# Flight_diagram.net
KiCad netlist of a schematic drawn in EAGLE
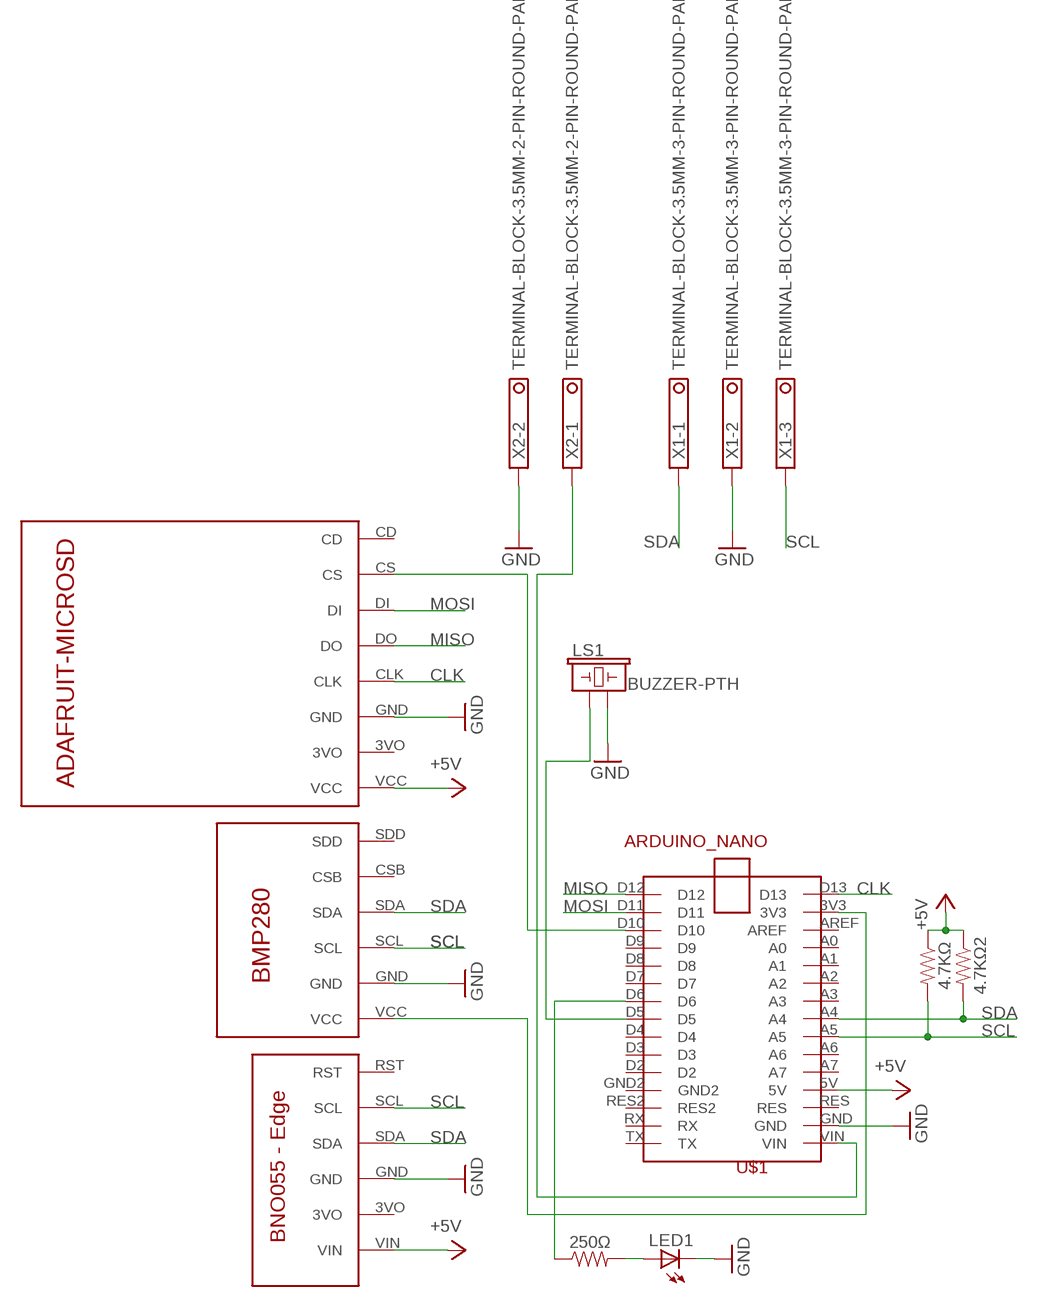
[diagram p0: schematic, sheet 1]

(export (version "E")
  (design (tool "Eeschema 10.0.6"))
  (components
    (comp (ref "4.7KΩ")
      (value "RESISTORAXIAL-0.3")
      (footprint "eagle-import:AXIAL-0.3")
      (libsource (lib "eagle-import") (part "RESISTORAXIAL-0.3"))
    )
    (comp (ref "4.7KΩ2")
      (value "RESISTORAXIAL-0.3")
      (footprint "eagle-import:AXIAL-0.3")
      (libsource (lib "eagle-import") (part "RESISTORAXIAL-0.3"))
    )
    (comp (ref "250Ω")
      (value "RESISTORAXIAL-0.3")
      (footprint "eagle-import:AXIAL-0.3")
      (libsource (lib "eagle-import") (part "RESISTORAXIAL-0.3"))
    )
    (comp (ref "LED1")
      (value "LED5MM")
      (footprint "eagle-import:LED5MM")
      (libsource (lib "eagle-import") (part "LED5MM"))
    )
    (comp (ref "LS1")
      (value "BUZZER-PTH")
      (footprint "eagle-import:BUZZER-12MM")
      (libsource (lib "eagle-import") (part "BUZZER-PTH"))
    )
    (comp (ref "U$1")
      (value "ARDUINO_NANO")
      (footprint "eagle-import:ARDUIN_NANO")
      (libsource (lib "eagle-import") (part "ARDUINO_NANO"))
    )
    (comp (ref "U$2")
      (value "BNO055")
      (footprint "eagle-import:BNO055")
      (libsource (lib "eagle-import") (part "BNO055"))
    )
    (comp (ref "U$3")
      (value "ADAFRUIT-MICROSD")
      (footprint "eagle-import:ADAFRUIT-MICROSD")
      (libsource (lib "eagle-import") (part "ADAFRUIT-MICROSD"))
    )
    (comp (ref "U$4")
      (value "BMP280")
      (footprint "eagle-import:BMP280")
      (libsource (lib "eagle-import") (part "BMP280"))
    )
    (comp (ref "X1")
      (value "TERMINAL-BLOCK-3.5MM-3-PIN-ROUND-PAD")
      (footprint "eagle-import:TERMINAL-BLOCK-3-PIN-3.5MM-ROUND-PAD")
      (libsource (lib "eagle-import") (part "TERMINAL-BLOCK-3.5MM-3-PIN-ROUND-PAD"))
    )
    (comp (ref "X2")
      (value "TERMINAL-BLOCK-3.5MM-2-PIN-ROUND-PAD")
      (footprint "eagle-import:TERMINAL-BLOCK-2-PIN-3.5MM-ROUND-PAD")
      (libsource (lib "eagle-import") (part "TERMINAL-BLOCK-3.5MM-2-PIN-ROUND-PAD"))
    )
  )
  (nets
    (net (code "1") (name "+5V") (class "Default")
      (node (ref "4.7KΩ") (pin "P$1") (pinfunction "1_P$1") (pintype "passive"))
      (node (ref "4.7KΩ2") (pin "P$1") (pinfunction "1_P$1") (pintype "passive"))
      (node (ref "U$1") (pin "5V") (pinfunction "5V_5V") (pintype "bidirectional"))
      (node (ref "U$2") (pin "VIN") (pinfunction "VIN_VIN") (pintype "bidirectional"))
      (node (ref "U$3") (pin "VCC") (pinfunction "VCC_VCC") (pintype "bidirectional"))
    )
    (net (code "2") (name "/CLK") (class "Default")
      (node (ref "U$1") (pin "D13") (pinfunction "D13_D13") (pintype "bidirectional"))
      (node (ref "U$3") (pin "CLK") (pinfunction "CLK_CLK") (pintype "bidirectional"))
    )
    (net (code "3") (name "/MISO") (class "Default")
      (node (ref "U$1") (pin "D12") (pinfunction "D12_D12") (pintype "bidirectional"))
      (node (ref "U$3") (pin "DO") (pinfunction "DO_DO") (pintype "bidirectional"))
    )
    (net (code "4") (name "/MOSI") (class "Default")
      (node (ref "U$1") (pin "D11") (pinfunction "D11_D11") (pintype "bidirectional"))
      (node (ref "U$3") (pin "DI") (pinfunction "DI_DI") (pintype "bidirectional"))
    )
    (net (code "5") (name "/SCL") (class "Default")
      (node (ref "4.7KΩ") (pin "P$2") (pinfunction "2_P$2") (pintype "passive"))
      (node (ref "U$1") (pin "A5") (pinfunction "A5_A5") (pintype "bidirectional"))
      (node (ref "U$2") (pin "SCL") (pinfunction "SCL_SCL") (pintype "bidirectional"))
      (node (ref "U$4") (pin "SCL") (pinfunction "SCL_SCL") (pintype "bidirectional"))
      (node (ref "X1") (pin "3") (pinfunction "K_3") (pintype "passive"))
    )
    (net (code "6") (name "/SDA") (class "Default")
      (node (ref "4.7KΩ2") (pin "P$2") (pinfunction "2_P$2") (pintype "passive"))
      (node (ref "U$1") (pin "A4") (pinfunction "A4_A4") (pintype "bidirectional"))
      (node (ref "U$2") (pin "SDA") (pinfunction "SDA_SDA") (pintype "bidirectional"))
      (node (ref "U$4") (pin "SDA") (pinfunction "SDA_SDA") (pintype "bidirectional"))
      (node (ref "X1") (pin "1") (pinfunction "K_1") (pintype "passive"))
    )
    (net (code "7") (name "GND") (class "Default")
      (node (ref "LED1") (pin "K") (pinfunction "C_K") (pintype "passive"))
      (node (ref "LS1") (pin "-") (pinfunction "2_-") (pintype "passive"))
      (node (ref "U$1") (pin "GND") (pinfunction "GND_GND") (pintype "bidirectional"))
      (node (ref "U$2") (pin "GND") (pinfunction "GND_GND") (pintype "bidirectional"))
      (node (ref "U$3") (pin "GND") (pinfunction "GND_GND") (pintype "bidirectional"))
      (node (ref "U$4") (pin "GND") (pinfunction "GND_GND") (pintype "bidirectional"))
      (node (ref "X1") (pin "2") (pinfunction "K_2") (pintype "passive"))
      (node (ref "X2") (pin "2") (pinfunction "K_2") (pintype "passive"))
    )
    (net (code "8") (name "Net-(250Ω-1)") (class "Default")
      (node (ref "250Ω") (pin "P$1") (pinfunction "1_P$1") (pintype "passive"))
      (node (ref "U$1") (pin "D6") (pinfunction "D6_D6") (pintype "bidirectional"))
    )
    (net (code "9") (name "Net-(250Ω-2)") (class "Default")
      (node (ref "250Ω") (pin "P$2") (pinfunction "2_P$2") (pintype "passive"))
      (node (ref "LED1") (pin "A") (pinfunction "A_A") (pintype "passive"))
    )
    (net (code "10") (name "Net-(LS1-1)") (class "Default")
      (node (ref "LS1") (pin "+") (pinfunction "1_+") (pintype "passive"))
      (node (ref "U$1") (pin "D5") (pinfunction "D5_D5") (pintype "bidirectional"))
    )
    (net (code "11") (name "Net-(U$1-Pad3V3)") (class "Default")
      (node (ref "U$1") (pin "3V3") (pinfunction "3V3_3V3") (pintype "bidirectional"))
      (node (ref "U$4") (pin "VCC") (pinfunction "VCC_VCC") (pintype "bidirectional"))
    )
    (net (code "12") (name "Net-(U$1-PadD10)") (class "Default")
      (node (ref "U$1") (pin "D10") (pinfunction "D10_D10") (pintype "bidirectional"))
      (node (ref "U$3") (pin "CS") (pinfunction "CS_CS") (pintype "bidirectional"))
    )
    (net (code "13") (name "Net-(X2A-K)") (class "Default")
      (node (ref "U$1") (pin "VIN") (pinfunction "VIN_VIN") (pintype "bidirectional"))
      (node (ref "X2") (pin "1") (pinfunction "K_1") (pintype "passive"))
    )
    (net (code "14") (name "unconnected-(U$1-PadA0)") (class "Default")
      (node (ref "U$1") (pin "A0") (pinfunction "A0_A0") (pintype "bidirectional"))
    )
    (net (code "15") (name "unconnected-(U$1-PadA1)") (class "Default")
      (node (ref "U$1") (pin "A1") (pinfunction "A1_A1") (pintype "bidirectional"))
    )
    (net (code "16") (name "unconnected-(U$1-PadA2)") (class "Default")
      (node (ref "U$1") (pin "A2") (pinfunction "A2_A2") (pintype "bidirectional"))
    )
    (net (code "17") (name "unconnected-(U$1-PadA3)") (class "Default")
      (node (ref "U$1") (pin "A3") (pinfunction "A3_A3") (pintype "bidirectional"))
    )
    (net (code "18") (name "unconnected-(U$1-PadA6)") (class "Default")
      (node (ref "U$1") (pin "A6") (pinfunction "A6_A6") (pintype "bidirectional"))
    )
    (net (code "19") (name "unconnected-(U$1-PadA7)") (class "Default")
      (node (ref "U$1") (pin "A7") (pinfunction "A7_A7") (pintype "bidirectional"))
    )
    (net (code "20") (name "unconnected-(U$1-PadAREF)") (class "Default")
      (node (ref "U$1") (pin "AREF") (pinfunction "AREF_AREF") (pintype "bidirectional"))
    )
    (net (code "21") (name "unconnected-(U$1-PadD2)") (class "Default")
      (node (ref "U$1") (pin "D2") (pinfunction "D2_D2") (pintype "bidirectional"))
    )
    (net (code "22") (name "unconnected-(U$1-PadD3)") (class "Default")
      (node (ref "U$1") (pin "D3") (pinfunction "D3_D3") (pintype "bidirectional"))
    )
    (net (code "23") (name "unconnected-(U$1-PadD4)") (class "Default")
      (node (ref "U$1") (pin "D4") (pinfunction "D4_D4") (pintype "bidirectional"))
    )
    (net (code "24") (name "unconnected-(U$1-PadD7)") (class "Default")
      (node (ref "U$1") (pin "D7") (pinfunction "D7_D7") (pintype "bidirectional"))
    )
    (net (code "25") (name "unconnected-(U$1-PadD8)") (class "Default")
      (node (ref "U$1") (pin "D8") (pinfunction "D8_D8") (pintype "bidirectional"))
    )
    (net (code "26") (name "unconnected-(U$1-PadD9)") (class "Default")
      (node (ref "U$1") (pin "D9") (pinfunction "D9_D9") (pintype "bidirectional"))
    )
    (net (code "27") (name "unconnected-(U$1-PadGND2)") (class "Default")
      (node (ref "U$1") (pin "GND2") (pinfunction "GND2_GND2") (pintype "bidirectional"))
    )
    (net (code "28") (name "unconnected-(U$1-PadRES)") (class "Default")
      (node (ref "U$1") (pin "RES") (pinfunction "RES_RES") (pintype "bidirectional"))
    )
    (net (code "29") (name "unconnected-(U$1-PadRES2)") (class "Default")
      (node (ref "U$1") (pin "RES2") (pinfunction "RES2_RES2") (pintype "bidirectional"))
    )
    (net (code "30") (name "unconnected-(U$1-PadRX)") (class "Default")
      (node (ref "U$1") (pin "RX") (pinfunction "RX_RX") (pintype "bidirectional"))
    )
    (net (code "31") (name "unconnected-(U$1-PadTX)") (class "Default")
      (node (ref "U$1") (pin "TX") (pinfunction "TX_TX") (pintype "bidirectional"))
    )
    (net (code "32") (name "unconnected-(U$2-Pad3VO)") (class "Default")
      (node (ref "U$2") (pin "3VO") (pinfunction "3VO_3VO") (pintype "bidirectional"))
    )
    (net (code "33") (name "unconnected-(U$2-PadRST)") (class "Default")
      (node (ref "U$2") (pin "RST") (pinfunction "RST_RST") (pintype "bidirectional"))
    )
    (net (code "34") (name "unconnected-(U$3-Pad3VO)") (class "Default")
      (node (ref "U$3") (pin "3VO") (pinfunction "3VO_3VO") (pintype "bidirectional"))
    )
    (net (code "35") (name "unconnected-(U$3-PadCD)") (class "Default")
      (node (ref "U$3") (pin "CD") (pinfunction "CD_CD") (pintype "bidirectional"))
    )
    (net (code "36") (name "unconnected-(U$4-PadCSB)") (class "Default")
      (node (ref "U$4") (pin "CSB") (pinfunction "CSB_CSB") (pintype "bidirectional"))
    )
    (net (code "37") (name "unconnected-(U$4-PadSDD)") (class "Default")
      (node (ref "U$4") (pin "SDD") (pinfunction "SDD_SDD") (pintype "bidirectional"))
    )
  )
)
